# v1.net
KiCad netlist of a schematic drawn in EAGLE
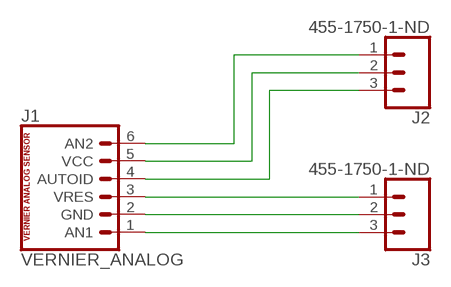
[diagram p0: schematic, sheet 1]

(export (version "E")
  (design (tool "Eeschema 10.0.6"))
  (components
    (comp (ref "J1")
      (value "VERNIER_ANALOG")
      (footprint "eagle-import:BTA")
      (libsource (lib "eagle-import") (part "VERNIER_ANALOG"))
    )
    (comp (ref "J2")
      (value "455-1750-1-ND")
      (footprint "eagle-import:1X03")
      (libsource (lib "eagle-import") (part "CONN_03"))
    )
    (comp (ref "J3")
      (value "455-1750-1-ND")
      (footprint "eagle-import:1X03")
      (libsource (lib "eagle-import") (part "CONN_03"))
    )
  )
  (nets
    (net (code "1") (name "Net-(J1-AN1)") (class "Default")
      (node (ref "J1") (pin "1") (pinfunction "AN1_1") (pintype "passive"))
      (node (ref "J3") (pin "3") (pinfunction "3_3") (pintype "passive"))
    )
    (net (code "2") (name "Net-(J1-AN2)") (class "Default")
      (node (ref "J1") (pin "6") (pinfunction "AN2_6") (pintype "passive"))
      (node (ref "J2") (pin "1") (pinfunction "1_1") (pintype "passive"))
    )
    (net (code "3") (name "Net-(J1-AUTOID)") (class "Default")
      (node (ref "J1") (pin "4") (pinfunction "AUTOID_4") (pintype "passive"))
      (node (ref "J2") (pin "3") (pinfunction "3_3") (pintype "passive"))
    )
    (net (code "4") (name "Net-(J1-GND)") (class "Default")
      (node (ref "J1") (pin "2") (pinfunction "GND_2") (pintype "passive"))
      (node (ref "J3") (pin "2") (pinfunction "2_2") (pintype "passive"))
    )
    (net (code "5") (name "Net-(J1-VCC)") (class "Default")
      (node (ref "J1") (pin "5") (pinfunction "VCC_5") (pintype "passive"))
      (node (ref "J2") (pin "2") (pinfunction "2_2") (pintype "passive"))
    )
    (net (code "6") (name "Net-(J1-VRES)") (class "Default")
      (node (ref "J1") (pin "3") (pinfunction "VRES_3") (pintype "passive"))
      (node (ref "J3") (pin "1") (pinfunction "1_1") (pintype "passive"))
    )
  )
)
